# Honig_Sensor_Board_2.net
KiCad netlist of a schematic drawn in EAGLE
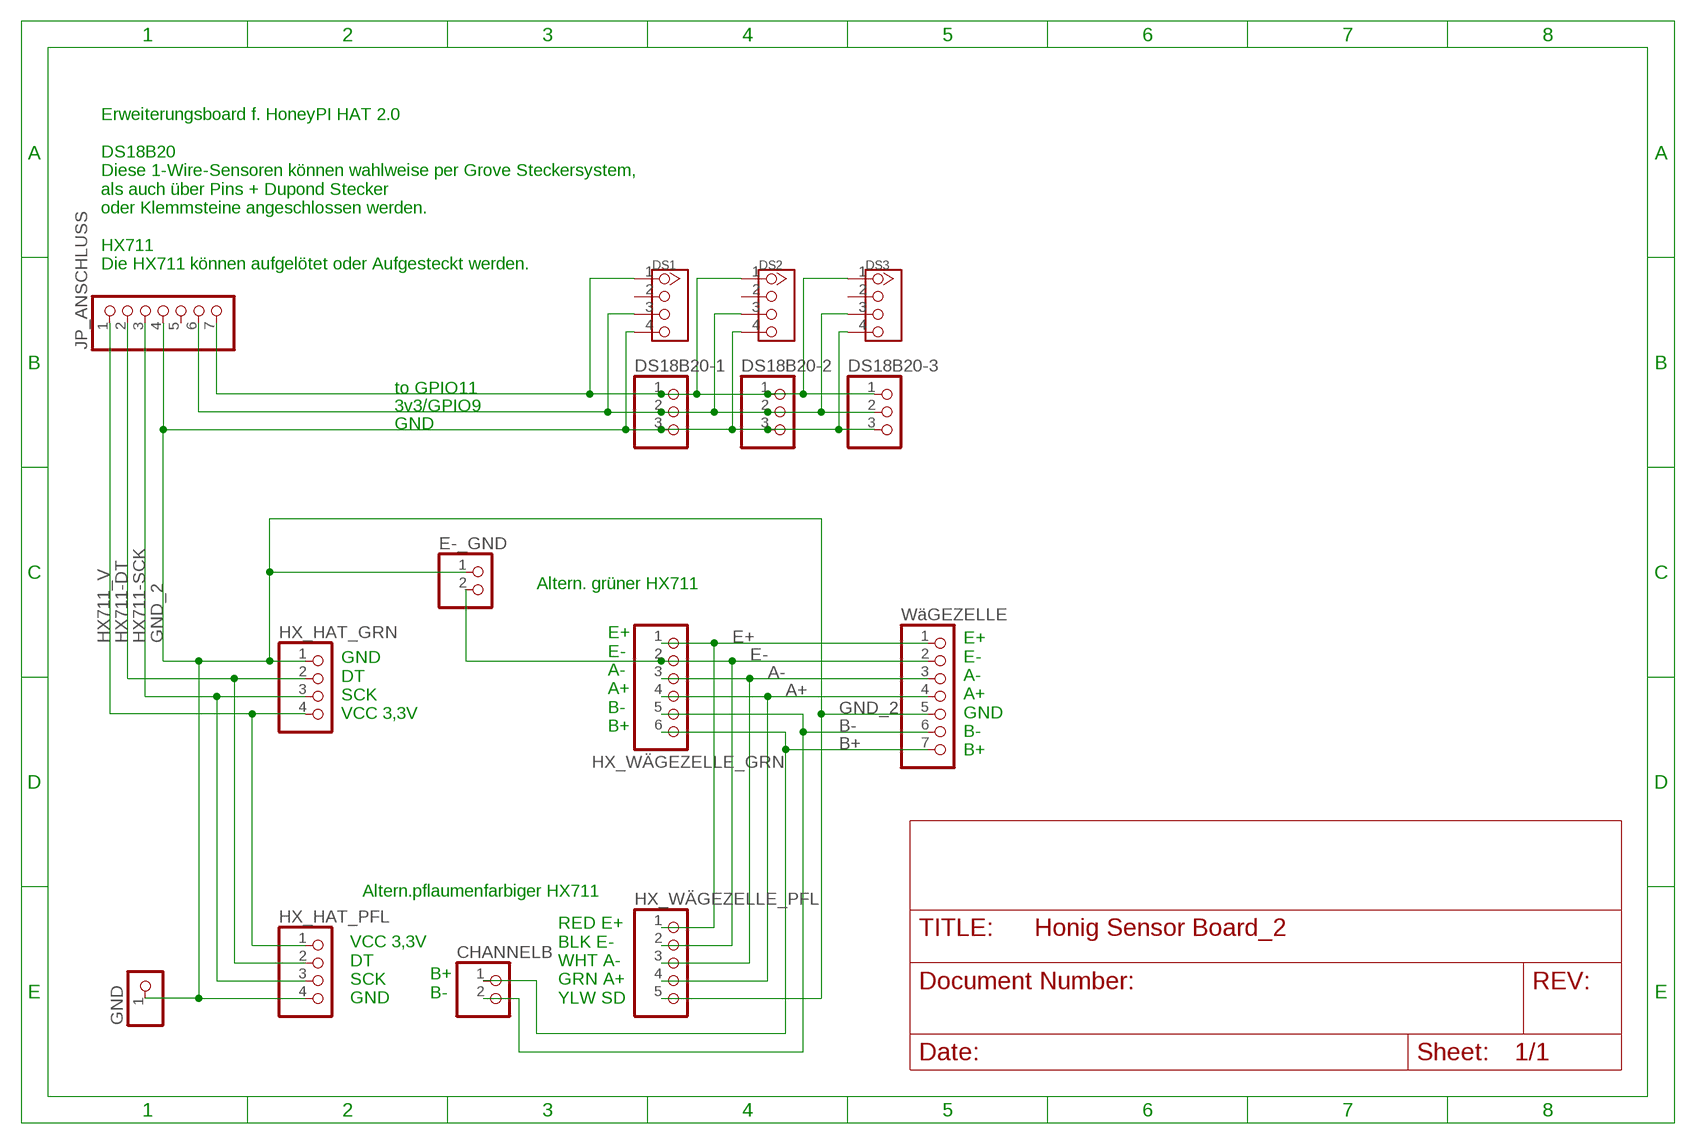
[diagram p0: schematic, sheet 1]

(export (version "E")
  (design (tool "Eeschema 10.0.6"))
  (components
    (comp (ref "CHANNELB")
      (value "PINHD-1X2")
      (footprint "eagle-import:1X02")
      (libsource (lib "eagle-import") (part "PINHD-1X2"))
    )
    (comp (ref "DS1")
      (value "TWIG-4P-2.0-2.0")
      (footprint "eagle-import:4P-2.0")
      (libsource (lib "eagle-import") (part "TWIG-4P-2.0-2.0"))
    )
    (comp (ref "DS2")
      (value "TWIG-4P-2.0-2.0")
      (footprint "eagle-import:4P-2.0")
      (libsource (lib "eagle-import") (part "TWIG-4P-2.0-2.0"))
    )
    (comp (ref "DS3")
      (value "TWIG-4P-2.0-2.0")
      (footprint "eagle-import:4P-2.0")
      (libsource (lib "eagle-import") (part "TWIG-4P-2.0-2.0"))
    )
    (comp (ref "DS18B20-1")
      (value "PINHD-1X3")
      (footprint "eagle-import:1X03")
      (libsource (lib "eagle-import") (part "PINHD-1X3"))
    )
    (comp (ref "DS18B20-2")
      (value "PINHD-1X3")
      (footprint "eagle-import:1X03")
      (libsource (lib "eagle-import") (part "PINHD-1X3"))
    )
    (comp (ref "DS18B20-3")
      (value "PINHD-1X3")
      (footprint "eagle-import:1X03")
      (libsource (lib "eagle-import") (part "PINHD-1X3"))
    )
    (comp (ref "E-_GND")
      (value "PINHD-1X2")
      (footprint "eagle-import:1X02")
      (libsource (lib "eagle-import") (part "PINHD-1X2"))
    )
    (comp (ref "GND")
      (value "PINHD-1X1")
      (footprint "eagle-import:1X01")
      (libsource (lib "eagle-import") (part "PINHD-1X1"))
    )
    (comp (ref "HX_HAT_GRN")
      (value "PINHD-1X4")
      (footprint "eagle-import:1X04")
      (libsource (lib "eagle-import") (part "PINHD-1X4"))
    )
    (comp (ref "HX_HAT_PFL")
      (value "PINHD-1X4")
      (footprint "eagle-import:1X04")
      (libsource (lib "eagle-import") (part "PINHD-1X4"))
    )
    (comp (ref "HX_WÄGEZELLE_GRN")
      (value "PINHD-1X6")
      (footprint "eagle-import:1X06")
      (libsource (lib "eagle-import") (part "PINHD-1X6"))
    )
    (comp (ref "HX_WÄGEZELLE_PFL")
      (value "PINHD-1X5")
      (footprint "eagle-import:1X05")
      (libsource (lib "eagle-import") (part "PINHD-1X5"))
    )
    (comp (ref "JP_ANSCHLUSS")
      (value "PINHD-1X7")
      (footprint "eagle-import:1X07")
      (libsource (lib "eagle-import") (part "PINHD-1X7"))
    )
    (comp (ref "WäGEZELLE")
      (value "PINHD-1X7")
      (footprint "eagle-import:1X07")
      (libsource (lib "eagle-import") (part "PINHD-1X7"))
    )
  )
  (nets
    (net (code "1") (name "/A+") (class "Default")
      (node (ref "HX_WÄGEZELLE_GRN") (pin "4") (pinfunction "4_4") (pintype "passive"))
      (node (ref "HX_WÄGEZELLE_PFL") (pin "4") (pinfunction "4_4") (pintype "passive"))
      (node (ref "WäGEZELLE") (pin "4") (pinfunction "4_4") (pintype "passive"))
    )
    (net (code "2") (name "/A-") (class "Default")
      (node (ref "HX_WÄGEZELLE_GRN") (pin "3") (pinfunction "3_3") (pintype "passive"))
      (node (ref "HX_WÄGEZELLE_PFL") (pin "3") (pinfunction "3_3") (pintype "passive"))
      (node (ref "WäGEZELLE") (pin "3") (pinfunction "3_3") (pintype "passive"))
    )
    (net (code "3") (name "/B+") (class "Default")
      (node (ref "CHANNELB") (pin "1") (pinfunction "1_1") (pintype "passive"))
      (node (ref "HX_WÄGEZELLE_GRN") (pin "6") (pinfunction "6_6") (pintype "passive"))
      (node (ref "WäGEZELLE") (pin "7") (pinfunction "7_7") (pintype "passive"))
    )
    (net (code "4") (name "/B-") (class "Default")
      (node (ref "CHANNELB") (pin "2") (pinfunction "2_2") (pintype "passive"))
      (node (ref "HX_WÄGEZELLE_GRN") (pin "5") (pinfunction "5_5") (pintype "passive"))
      (node (ref "WäGEZELLE") (pin "6") (pinfunction "6_6") (pintype "passive"))
    )
    (net (code "5") (name "/E+") (class "Default")
      (node (ref "HX_WÄGEZELLE_GRN") (pin "1") (pinfunction "1_1") (pintype "passive"))
      (node (ref "HX_WÄGEZELLE_PFL") (pin "1") (pinfunction "1_1") (pintype "passive"))
      (node (ref "WäGEZELLE") (pin "1") (pinfunction "1_1") (pintype "passive"))
    )
    (net (code "6") (name "/E-") (class "Default")
      (node (ref "E-_GND") (pin "2") (pinfunction "2_2") (pintype "passive"))
      (node (ref "HX_WÄGEZELLE_GRN") (pin "2") (pinfunction "2_2") (pintype "passive"))
      (node (ref "HX_WÄGEZELLE_PFL") (pin "2") (pinfunction "2_2") (pintype "passive"))
      (node (ref "WäGEZELLE") (pin "2") (pinfunction "2_2") (pintype "passive"))
    )
    (net (code "7") (name "/GND_2") (class "Default")
      (node (ref "DS1") (pin "4") (pinfunction "4_4") (pintype "bidirectional"))
      (node (ref "DS18B20-1") (pin "3") (pinfunction "3_3") (pintype "passive"))
      (node (ref "DS18B20-2") (pin "3") (pinfunction "3_3") (pintype "passive"))
      (node (ref "DS18B20-3") (pin "3") (pinfunction "3_3") (pintype "passive"))
      (node (ref "DS2") (pin "4") (pinfunction "4_4") (pintype "bidirectional"))
      (node (ref "DS3") (pin "4") (pinfunction "4_4") (pintype "bidirectional"))
      (node (ref "E-_GND") (pin "1") (pinfunction "1_1") (pintype "passive"))
      (node (ref "GND") (pin "1") (pinfunction "1_1") (pintype "passive"))
      (node (ref "HX_HAT_GRN") (pin "1") (pinfunction "1_1") (pintype "passive"))
      (node (ref "HX_HAT_PFL") (pin "4") (pinfunction "4_4") (pintype "passive"))
      (node (ref "HX_WÄGEZELLE_PFL") (pin "5") (pinfunction "5_5") (pintype "passive"))
      (node (ref "JP_ANSCHLUSS") (pin "4") (pinfunction "4_4") (pintype "passive"))
      (node (ref "WäGEZELLE") (pin "5") (pinfunction "5_5") (pintype "passive"))
    )
    (net (code "8") (name "/HX711-DT") (class "Default")
      (node (ref "HX_HAT_GRN") (pin "2") (pinfunction "2_2") (pintype "passive"))
      (node (ref "HX_HAT_PFL") (pin "2") (pinfunction "2_2") (pintype "passive"))
      (node (ref "JP_ANSCHLUSS") (pin "2") (pinfunction "2_2") (pintype "passive"))
    )
    (net (code "9") (name "/HX711-SCK") (class "Default")
      (node (ref "HX_HAT_GRN") (pin "3") (pinfunction "3_3") (pintype "passive"))
      (node (ref "HX_HAT_PFL") (pin "3") (pinfunction "3_3") (pintype "passive"))
      (node (ref "JP_ANSCHLUSS") (pin "3") (pinfunction "3_3") (pintype "passive"))
    )
    (net (code "10") (name "/HX711_V") (class "Default")
      (node (ref "HX_HAT_GRN") (pin "4") (pinfunction "4_4") (pintype "passive"))
      (node (ref "HX_HAT_PFL") (pin "1") (pinfunction "1_1") (pintype "passive"))
      (node (ref "JP_ANSCHLUSS") (pin "1") (pinfunction "1_1") (pintype "passive"))
    )
    (net (code "11") (name "Net-(DS1-Pad1)") (class "Default")
      (node (ref "DS1") (pin "1") (pinfunction "1_1") (pintype "bidirectional"))
      (node (ref "DS18B20-1") (pin "1") (pinfunction "1_1") (pintype "passive"))
      (node (ref "DS18B20-2") (pin "1") (pinfunction "1_1") (pintype "passive"))
      (node (ref "DS18B20-3") (pin "1") (pinfunction "1_1") (pintype "passive"))
      (node (ref "DS2") (pin "1") (pinfunction "1_1") (pintype "bidirectional"))
      (node (ref "DS3") (pin "1") (pinfunction "1_1") (pintype "bidirectional"))
      (node (ref "JP_ANSCHLUSS") (pin "7") (pinfunction "7_7") (pintype "passive"))
    )
    (net (code "12") (name "Net-(DS1-Pad3)") (class "Default")
      (node (ref "DS1") (pin "3") (pinfunction "3_3") (pintype "bidirectional"))
      (node (ref "DS18B20-1") (pin "2") (pinfunction "2_2") (pintype "passive"))
      (node (ref "DS18B20-2") (pin "2") (pinfunction "2_2") (pintype "passive"))
      (node (ref "DS18B20-3") (pin "2") (pinfunction "2_2") (pintype "passive"))
      (node (ref "DS2") (pin "3") (pinfunction "3_3") (pintype "bidirectional"))
      (node (ref "DS3") (pin "3") (pinfunction "3_3") (pintype "bidirectional"))
      (node (ref "JP_ANSCHLUSS") (pin "6") (pinfunction "6_6") (pintype "passive"))
    )
    (net (code "13") (name "unconnected-(DS1-Pad2)") (class "Default")
      (node (ref "DS1") (pin "2") (pinfunction "2_2") (pintype "bidirectional"))
    )
    (net (code "14") (name "unconnected-(DS2-Pad2)") (class "Default")
      (node (ref "DS2") (pin "2") (pinfunction "2_2") (pintype "bidirectional"))
    )
    (net (code "15") (name "unconnected-(DS3-Pad2)") (class "Default")
      (node (ref "DS3") (pin "2") (pinfunction "2_2") (pintype "bidirectional"))
    )
    (net (code "16") (name "unconnected-(JP_ANSCHLUSS-Pad5)") (class "Default")
      (node (ref "JP_ANSCHLUSS") (pin "5") (pinfunction "5_5") (pintype "passive"))
    )
  )
)
